# proto-bike-light.net
KiCad netlist of a schematic drawn in EAGLE
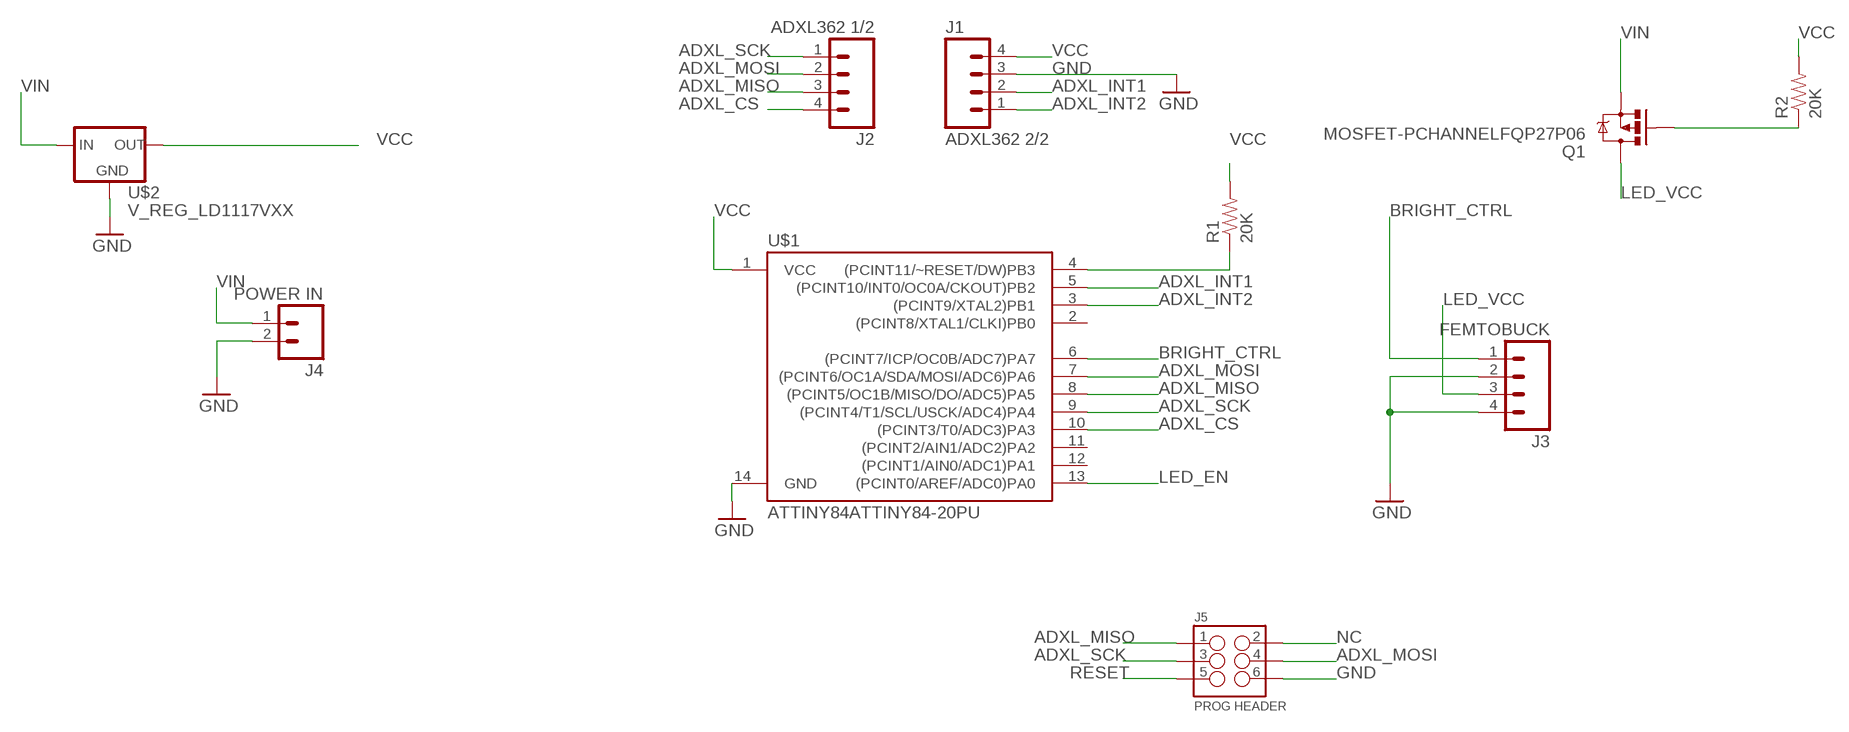
[diagram p0: schematic, sheet 1]

(export (version "E")
  (design (tool "Eeschema 10.0.6"))
  (components
    (comp (ref "J1")
      (value "ADXL362 2/2")
      (footprint "eagle-import:1X04")
      (libsource (lib "eagle-import") (part "M04PTH"))
    )
    (comp (ref "J2")
      (value "ADXL362 1/2")
      (footprint "eagle-import:1X04")
      (libsource (lib "eagle-import") (part "M04PTH"))
    )
    (comp (ref "J3")
      (value "FEMTOBUCK")
      (footprint "eagle-import:1X04")
      (libsource (lib "eagle-import") (part "M04PTH"))
    )
    (comp (ref "J4")
      (value "POWER IN")
      (footprint "eagle-import:1X02")
      (libsource (lib "eagle-import") (part "M02PTH"))
    )
    (comp (ref "J5")
      (value "PROG HEADER")
      (footprint "eagle-import:2X3")
      (libsource (lib "eagle-import") (part "M03X2FEMALE"))
    )
    (comp (ref "Q1")
      (value "MOSFET-PCHANNELFQP27P06")
      (footprint "eagle-import:TO220V")
      (libsource (lib "eagle-import") (part "MOSFET-PCHANNELFQP27P06"))
    )
    (comp (ref "R1")
      (value "20K")
      (footprint "eagle-import:AXIAL-0.4")
      (libsource (lib "eagle-import") (part "RESISTORPTH-1/4W"))
    )
    (comp (ref "R2")
      (value "20K")
      (footprint "eagle-import:AXIAL-0.4")
      (libsource (lib "eagle-import") (part "RESISTORPTH-1/4W"))
    )
    (comp (ref "U$1")
      (value "ATTINY84ATTINY84-20PU")
      (footprint "eagle-import:DIL14")
      (libsource (lib "eagle-import") (part "ATTINY84ATTINY84-20PU"))
    )
    (comp (ref "U$2")
      (value "V_REG_LD1117VXX")
      (footprint "eagle-import:78XXL")
      (libsource (lib "eagle-import") (part "V_REG_LD1117VXX"))
    )
  )
  (nets
    (net (code "1") (name "/ADXL_CS") (class "Default")
      (node (ref "J2") (pin "4") (pinfunction "4_4") (pintype "passive"))
      (node (ref "U$1") (pin "10") (pinfunction "(PCINT3/T0/ADC3)PA3_10") (pintype "bidirectional"))
    )
    (net (code "2") (name "/ADXL_INT1") (class "Default")
      (node (ref "J1") (pin "2") (pinfunction "2_2") (pintype "passive"))
      (node (ref "U$1") (pin "5") (pinfunction "(PCINT10/INT0/OC0A/CKOUT)PB2_5") (pintype "bidirectional"))
    )
    (net (code "3") (name "/ADXL_INT2") (class "Default")
      (node (ref "J1") (pin "1") (pinfunction "1_1") (pintype "passive"))
      (node (ref "U$1") (pin "3") (pinfunction "(PCINT9/XTAL2)PB1_3") (pintype "bidirectional"))
    )
    (net (code "4") (name "/ADXL_MISO") (class "Default")
      (node (ref "J2") (pin "3") (pinfunction "3_3") (pintype "passive"))
      (node (ref "J5") (pin "1") (pinfunction "1_1") (pintype "bidirectional"))
      (node (ref "U$1") (pin "8") (pinfunction "(PCINT5/OC1B/MISO/DO/ADC5)PA5_8") (pintype "bidirectional"))
    )
    (net (code "5") (name "/ADXL_MOSI") (class "Default")
      (node (ref "J2") (pin "2") (pinfunction "2_2") (pintype "passive"))
      (node (ref "J5") (pin "4") (pinfunction "4_4") (pintype "bidirectional"))
      (node (ref "U$1") (pin "7") (pinfunction "(PCINT6/OC1A/SDA/MOSI/ADC6)PA6_7") (pintype "bidirectional"))
    )
    (net (code "6") (name "/ADXL_SCK") (class "Default")
      (node (ref "J2") (pin "1") (pinfunction "1_1") (pintype "passive"))
      (node (ref "J5") (pin "3") (pinfunction "3_3") (pintype "bidirectional"))
      (node (ref "U$1") (pin "9") (pinfunction "(PCINT4/T1/SCL/USCK/ADC4)PA4_9") (pintype "bidirectional"))
    )
    (net (code "7") (name "/BRIGHT_CTRL") (class "Default")
      (node (ref "J3") (pin "1") (pinfunction "1_1") (pintype "passive"))
      (node (ref "U$1") (pin "6") (pinfunction "(PCINT7/ICP/OC0B/ADC7)PA7_6") (pintype "bidirectional"))
    )
    (net (code "8") (name "/LED_EN") (class "Default")
      (node (ref "Q1") (pin "1") (pinfunction "G_1") (pintype "passive"))
      (node (ref "R2") (pin "P$1") (pinfunction "1_P$1") (pintype "passive"))
      (node (ref "U$1") (pin "13") (pinfunction "(PCINT0/AREF/ADC0)PA0_13") (pintype "bidirectional"))
    )
    (net (code "9") (name "/LED_VCC") (class "Default")
      (node (ref "J3") (pin "3") (pinfunction "3_3") (pintype "passive"))
      (node (ref "Q1") (pin "2") (pinfunction "D_2") (pintype "passive"))
    )
    (net (code "10") (name "/NC") (class "Default")
      (node (ref "J5") (pin "2") (pinfunction "2_2") (pintype "bidirectional"))
    )
    (net (code "11") (name "/RESET") (class "Default")
      (node (ref "J5") (pin "5") (pinfunction "5_5") (pintype "bidirectional"))
      (node (ref "R1") (pin "P$1") (pinfunction "1_P$1") (pintype "passive"))
      (node (ref "U$1") (pin "4") (pinfunction "(PCINT11/~{RESET/DW})PB3_4") (pintype "bidirectional"))
    )
    (net (code "12") (name "/VCC") (class "Default")
      (node (ref "J1") (pin "4") (pinfunction "4_4") (pintype "passive"))
      (node (ref "R1") (pin "P$2") (pinfunction "2_P$2") (pintype "passive"))
      (node (ref "R2") (pin "P$2") (pinfunction "2_P$2") (pintype "passive"))
      (node (ref "U$1") (pin "1") (pinfunction "VCC_1") (pintype "bidirectional"))
      (node (ref "U$2") (pin "GND") (pinfunction "OUT_GND") (pintype "passive"))
    )
    (net (code "13") (name "/VIN") (class "Default")
      (node (ref "J4") (pin "1") (pinfunction "1_1") (pintype "passive"))
      (node (ref "Q1") (pin "3") (pinfunction "S_3") (pintype "passive"))
      (node (ref "U$2") (pin "OUT") (pinfunction "IN_OUT") (pintype "input"))
    )
    (net (code "14") (name "GND") (class "Default")
      (node (ref "J1") (pin "3") (pinfunction "3_3") (pintype "passive"))
      (node (ref "J3") (pin "2") (pinfunction "2_2") (pintype "passive"))
      (node (ref "J3") (pin "4") (pinfunction "4_4") (pintype "passive"))
      (node (ref "J4") (pin "2") (pinfunction "2_2") (pintype "passive"))
      (node (ref "J5") (pin "6") (pinfunction "6_6") (pintype "bidirectional"))
      (node (ref "U$1") (pin "14") (pinfunction "GND_14") (pintype "bidirectional"))
      (node (ref "U$2") (pin "IN") (pinfunction "GND_IN") (pintype "input"))
    )
    (net (code "15") (name "unconnected-(U$1-(PCINT1{slash}AIN0{slash}ADC1)PA1-Pad12)") (class "Default")
      (node (ref "U$1") (pin "12") (pinfunction "(PCINT1/AIN0/ADC1)PA1_12") (pintype "bidirectional"))
    )
    (net (code "16") (name "unconnected-(U$1-(PCINT2{slash}AIN1{slash}ADC2)PA2-Pad11)") (class "Default")
      (node (ref "U$1") (pin "11") (pinfunction "(PCINT2/AIN1/ADC2)PA2_11") (pintype "bidirectional"))
    )
    (net (code "17") (name "unconnected-(U$1-(PCINT8{slash}XTAL1{slash}CLKI)PB0-Pad2)") (class "Default")
      (node (ref "U$1") (pin "2") (pinfunction "(PCINT8/XTAL1/CLKI)PB0_2") (pintype "bidirectional"))
    )
  )
)
